# AT25EU_-_16_MBit_SPI.net
KiCad netlist of a schematic drawn in Altium Designer
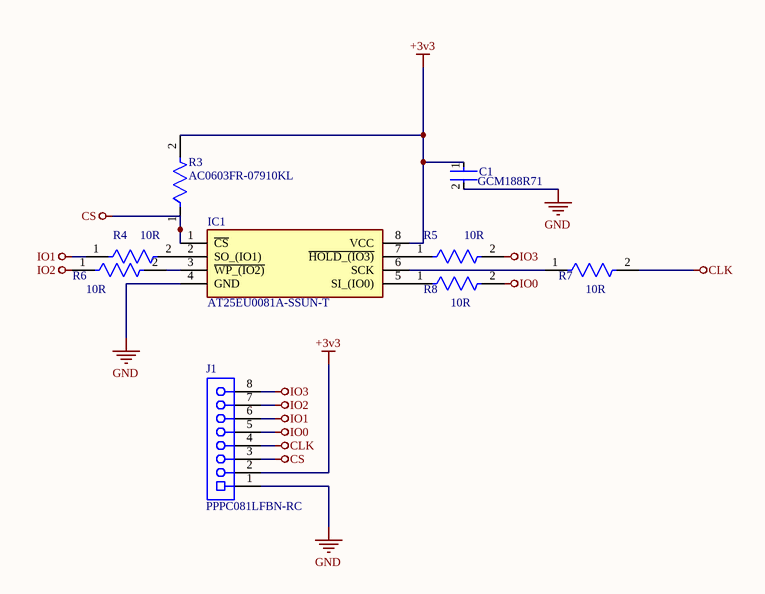
[diagram p0: AT25EU - 16 MBit SPI.SchDoc]

(export (version "E")
  (design (tool "Eeschema 10.0.6"))
  (components
    (comp (ref "C1")
      (value "GCM188R71")
      (footprint "FP-GCM188-0_1-IPC_B")
      (description "Ceramic Capacitor for Automotive 1uF  ±10% 16VDC X7R 0603 Paper T/R")
      (fields (field (name "VOLTAGE") "16V") (field (name "TOLERANCE") "10%"))
      (libsource (lib "Altium Content Vault") (part "02cd4be3c70576c341d710602a673aa"))
    )
    (comp (ref "IC1")
      (value "AT25EU0081A-SSUN-T")
      (footprint "SamacSys:SOIC127P600X175-8N")
      (description "Integrated Circuit")
      (libsource (lib "SamacSys") (part "AT25EU0081A-SSUN-T"))
    )
    (comp (ref "J1")
      (value "PPPC081LFBN-RC")
      (footprint "SLIN-PPPC081LFBN-RC_V")
      (fields (field (name "MANUFACTURER") "Sullins"))
      (libsource (lib "CubeSat Team") (part "CN-1P-F-R8"))
    )
    (comp (ref "R3")
      (value "AC0603FR-07910KL")
      (footprint "FP-AC0603-IPC_B")
      (description "RES 910KΩ 1.00% 0.1W 0603")
      (fields (field (name "TOLERANCE") "1%"))
      (libsource (lib "Altium Content Vault") (part "1029c3af85768c4190bb7ad29bc67b5"))
    )
    (comp (ref "R4")
      (value "10R")
      (footprint "FP-AC0603-MFG")
      (description "RES 10Ω 1.00% 0.1W 0603")
      (fields (field (name "TOLERANCE") "1%"))
      (libsource (lib "Altium Content Vault") (part "1029c3af85768c4190bb7ad29bc67b5"))
    )
    (comp (ref "R5")
      (value "10R")
      (footprint "FP-AC0603-MFG")
      (description "RES 10Ω 1.00% 0.1W 0603")
      (fields (field (name "TOLERANCE") "1%"))
      (libsource (lib "Altium Content Vault") (part "1029c3af85768c4190bb7ad29bc67b5"))
    )
    (comp (ref "R6")
      (value "10R")
      (footprint "FP-AC0603-MFG")
      (description "RES 10Ω 1.00% 0.1W 0603")
      (fields (field (name "TOLERANCE") "1%"))
      (libsource (lib "Altium Content Vault") (part "1029c3af85768c4190bb7ad29bc67b5"))
    )
    (comp (ref "R7")
      (value "10R")
      (footprint "FP-AC0603-MFG")
      (description "RES 10Ω 1.00% 0.1W 0603")
      (fields (field (name "TOLERANCE") "1%"))
      (libsource (lib "Altium Content Vault") (part "1029c3af85768c4190bb7ad29bc67b5"))
    )
    (comp (ref "R8")
      (value "10R")
      (footprint "FP-AC0603-MFG")
      (description "RES 10Ω 1.00% 0.1W 0603")
      (fields (field (name "TOLERANCE") "1%"))
      (libsource (lib "Altium Content Vault") (part "1029c3af85768c4190bb7ad29bc67b5"))
    )
  )
  (nets
    (net (code "1") (name "+3v3") (class "Default")
      (node (ref "C1") (pin "1") (pinfunction "1_1") (pintype "passive"))
      (node (ref "IC1") (pin "8") (pinfunction "VCC_8") (pintype "passive"))
      (node (ref "J1") (pin "2") (pinfunction "2_2") (pintype "passive"))
      (node (ref "R3") (pin "2") (pinfunction "2_2") (pintype "passive"))
    )
    (net (code "2") (name "CLK") (class "Default")
      (node (ref "J1") (pin "4") (pinfunction "4_4") (pintype "passive"))
      (node (ref "R7") (pin "2") (pinfunction "2_2") (pintype "passive"))
    )
    (net (code "3") (name "CS") (class "Default")
      (node (ref "IC1") (pin "1") (pinfunction "~{CS}_1") (pintype "passive"))
      (node (ref "J1") (pin "3") (pinfunction "3_3") (pintype "passive"))
      (node (ref "R3") (pin "1") (pinfunction "1_1") (pintype "passive"))
    )
    (net (code "4") (name "GND") (class "Default")
      (node (ref "C1") (pin "2") (pinfunction "2_2") (pintype "passive"))
      (node (ref "IC1") (pin "4") (pinfunction "GND_4") (pintype "passive"))
      (node (ref "J1") (pin "1") (pinfunction "1_1") (pintype "passive"))
    )
    (net (code "5") (name "IO0") (class "Default")
      (node (ref "J1") (pin "5") (pinfunction "5_5") (pintype "passive"))
      (node (ref "R8") (pin "2") (pinfunction "2_2") (pintype "passive"))
    )
    (net (code "6") (name "IO1") (class "Default")
      (node (ref "J1") (pin "6") (pinfunction "6_6") (pintype "passive"))
      (node (ref "R4") (pin "1") (pinfunction "1_1") (pintype "passive"))
    )
    (net (code "7") (name "IO2") (class "Default")
      (node (ref "J1") (pin "7") (pinfunction "7_7") (pintype "passive"))
      (node (ref "R6") (pin "1") (pinfunction "1_1") (pintype "passive"))
    )
    (net (code "8") (name "IO3") (class "Default")
      (node (ref "J1") (pin "8") (pinfunction "8_8") (pintype "passive"))
      (node (ref "R5") (pin "2") (pinfunction "2_2") (pintype "passive"))
    )
    (net (code "9") (name "Net-(IC1-SCK)") (class "Default")
      (node (ref "IC1") (pin "6") (pinfunction "SCK_6") (pintype "passive"))
      (node (ref "R7") (pin "1") (pinfunction "1_1") (pintype "passive"))
    )
    (net (code "10") (name "Net-(IC1-SI_(IO0))") (class "Default")
      (node (ref "IC1") (pin "5") (pinfunction "SI_(IO0)_5") (pintype "passive"))
      (node (ref "R8") (pin "1") (pinfunction "1_1") (pintype "passive"))
    )
    (net (code "11") (name "Net-(IC1-SO_(IO1))") (class "Default")
      (node (ref "IC1") (pin "2") (pinfunction "SO_(IO1)_2") (pintype "passive"))
      (node (ref "R4") (pin "2") (pinfunction "2_2") (pintype "passive"))
    )
    (net (code "12") (name "Net-(IC1-~{HOLD_(IO3)})") (class "Default")
      (node (ref "IC1") (pin "7") (pinfunction "~{HOLD_(IO3)}_7") (pintype "passive"))
      (node (ref "R5") (pin "1") (pinfunction "1_1") (pintype "passive"))
    )
    (net (code "13") (name "Net-(IC1-~{WP_(IO2)})") (class "Default")
      (node (ref "IC1") (pin "3") (pinfunction "~{WP_(IO2)}_3") (pintype "passive"))
      (node (ref "R6") (pin "2") (pinfunction "2_2") (pintype "passive"))
    )
  )
)
